# confBadgeV1.net
KiCad netlist of a schematic drawn in EAGLE
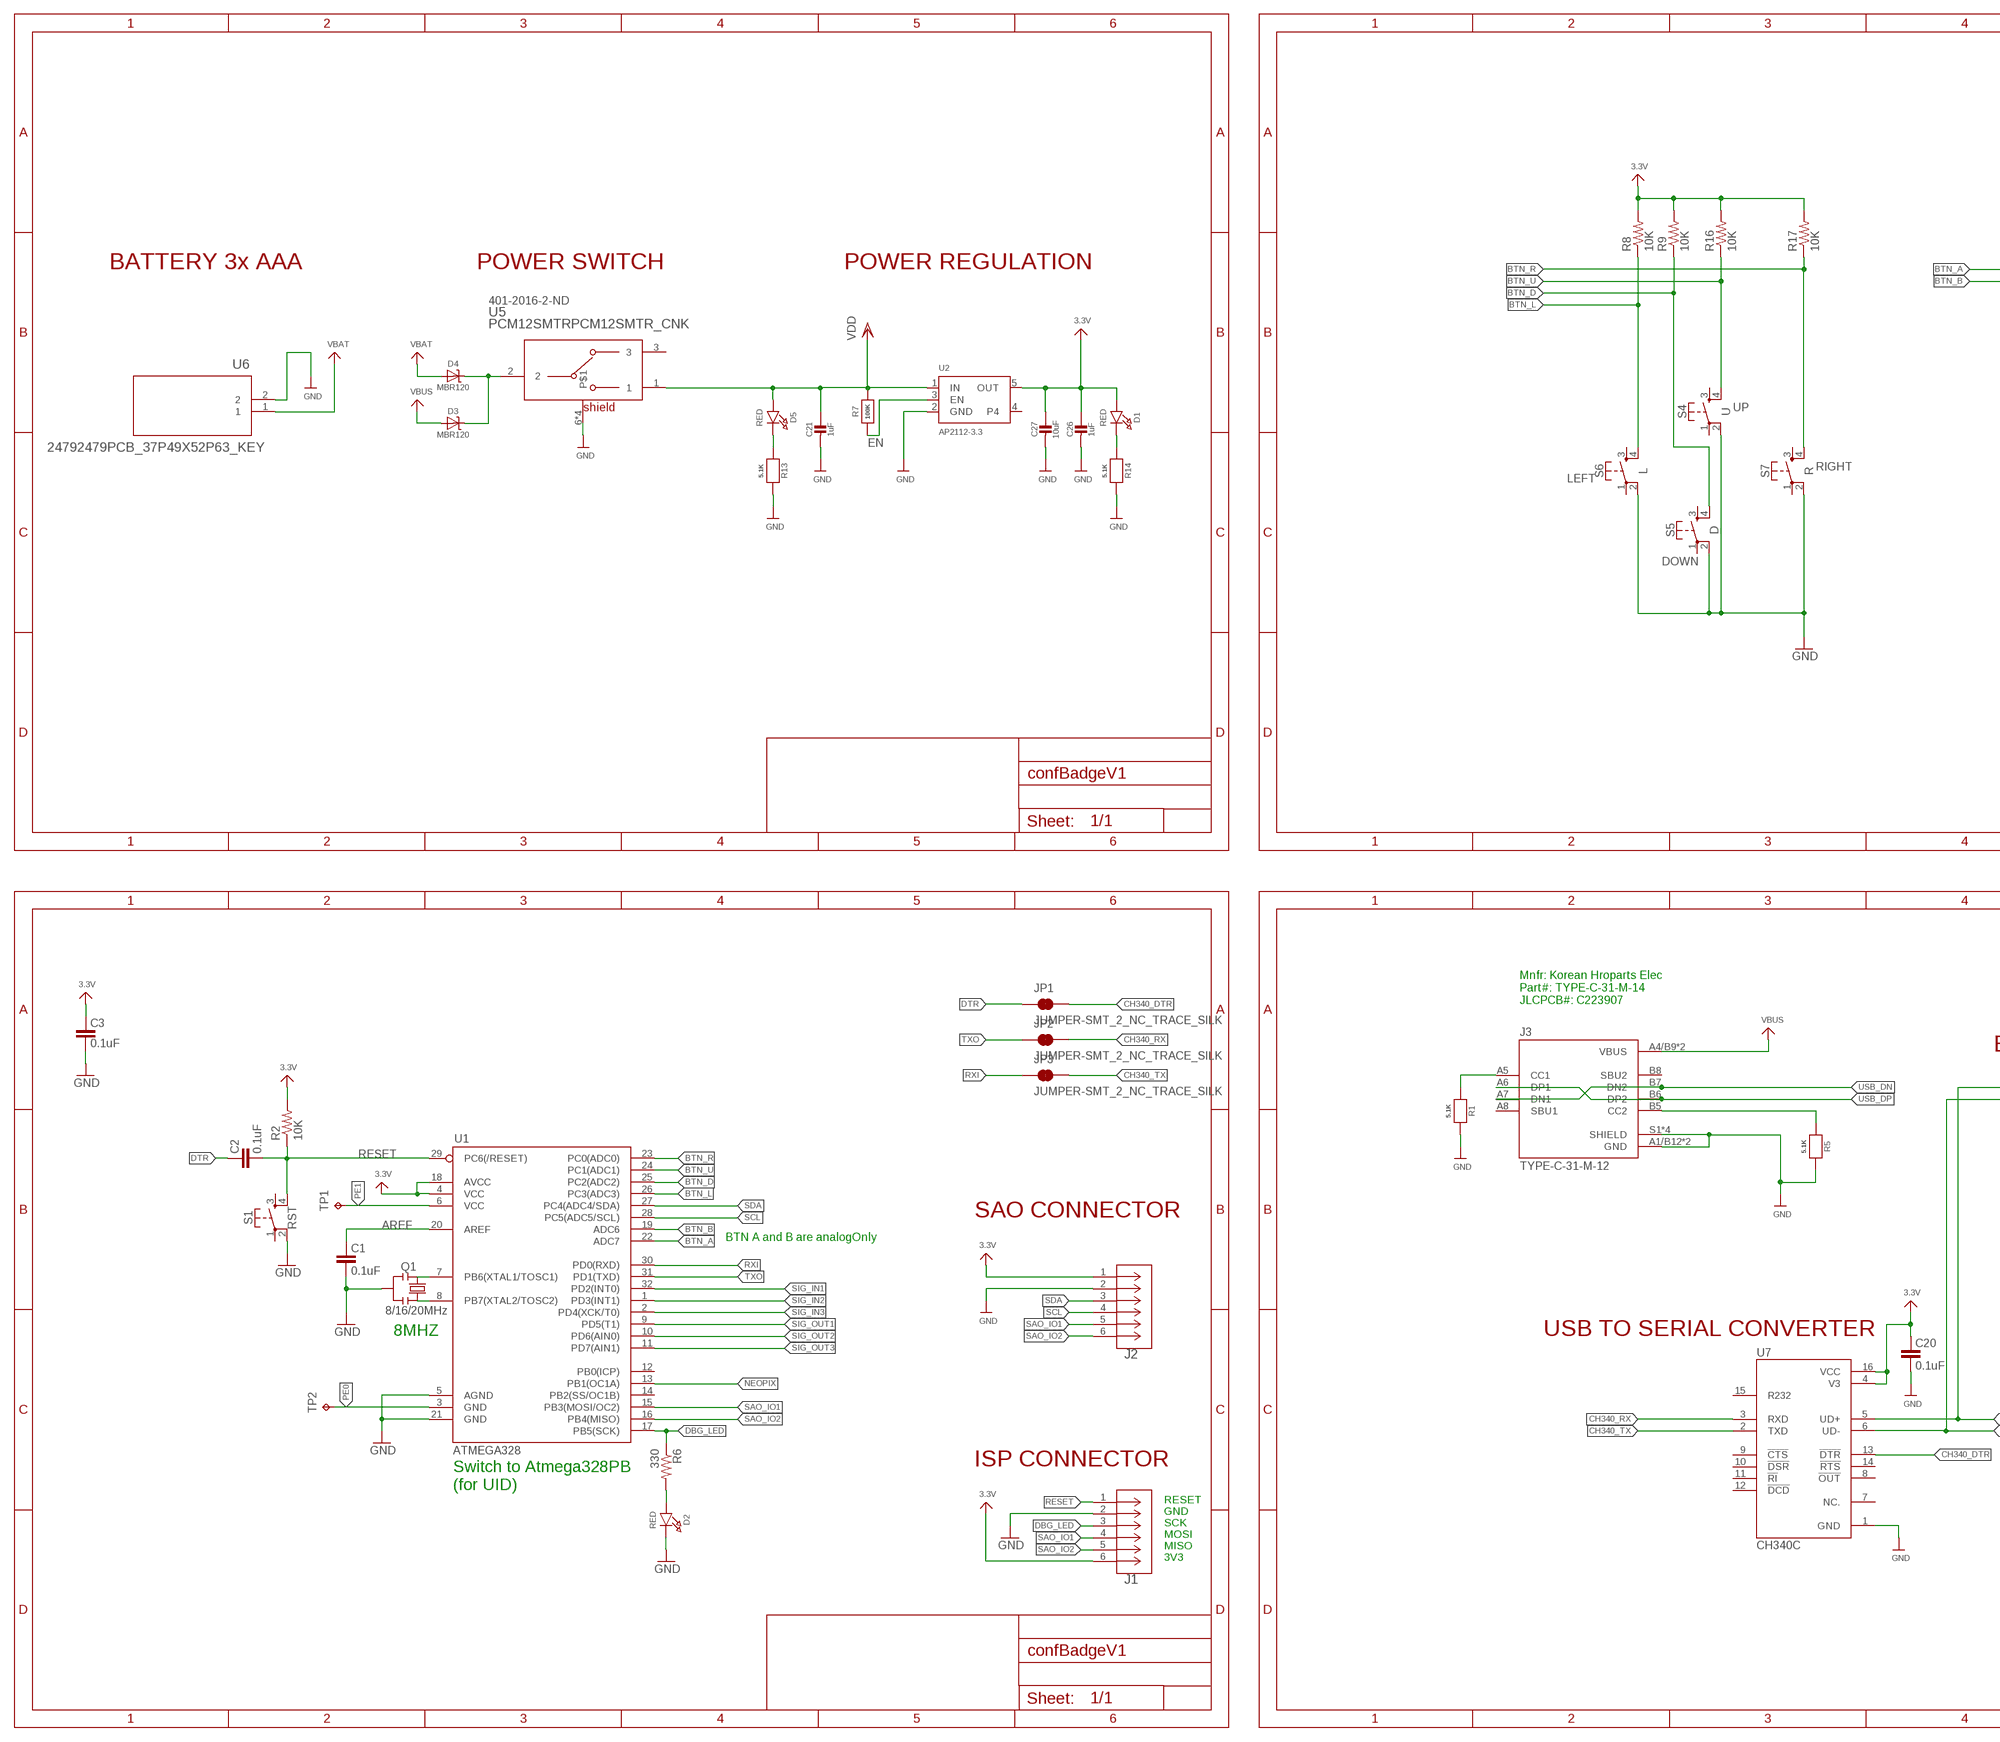
[diagram p0: schematic, sheet 1, part 1 of 2]
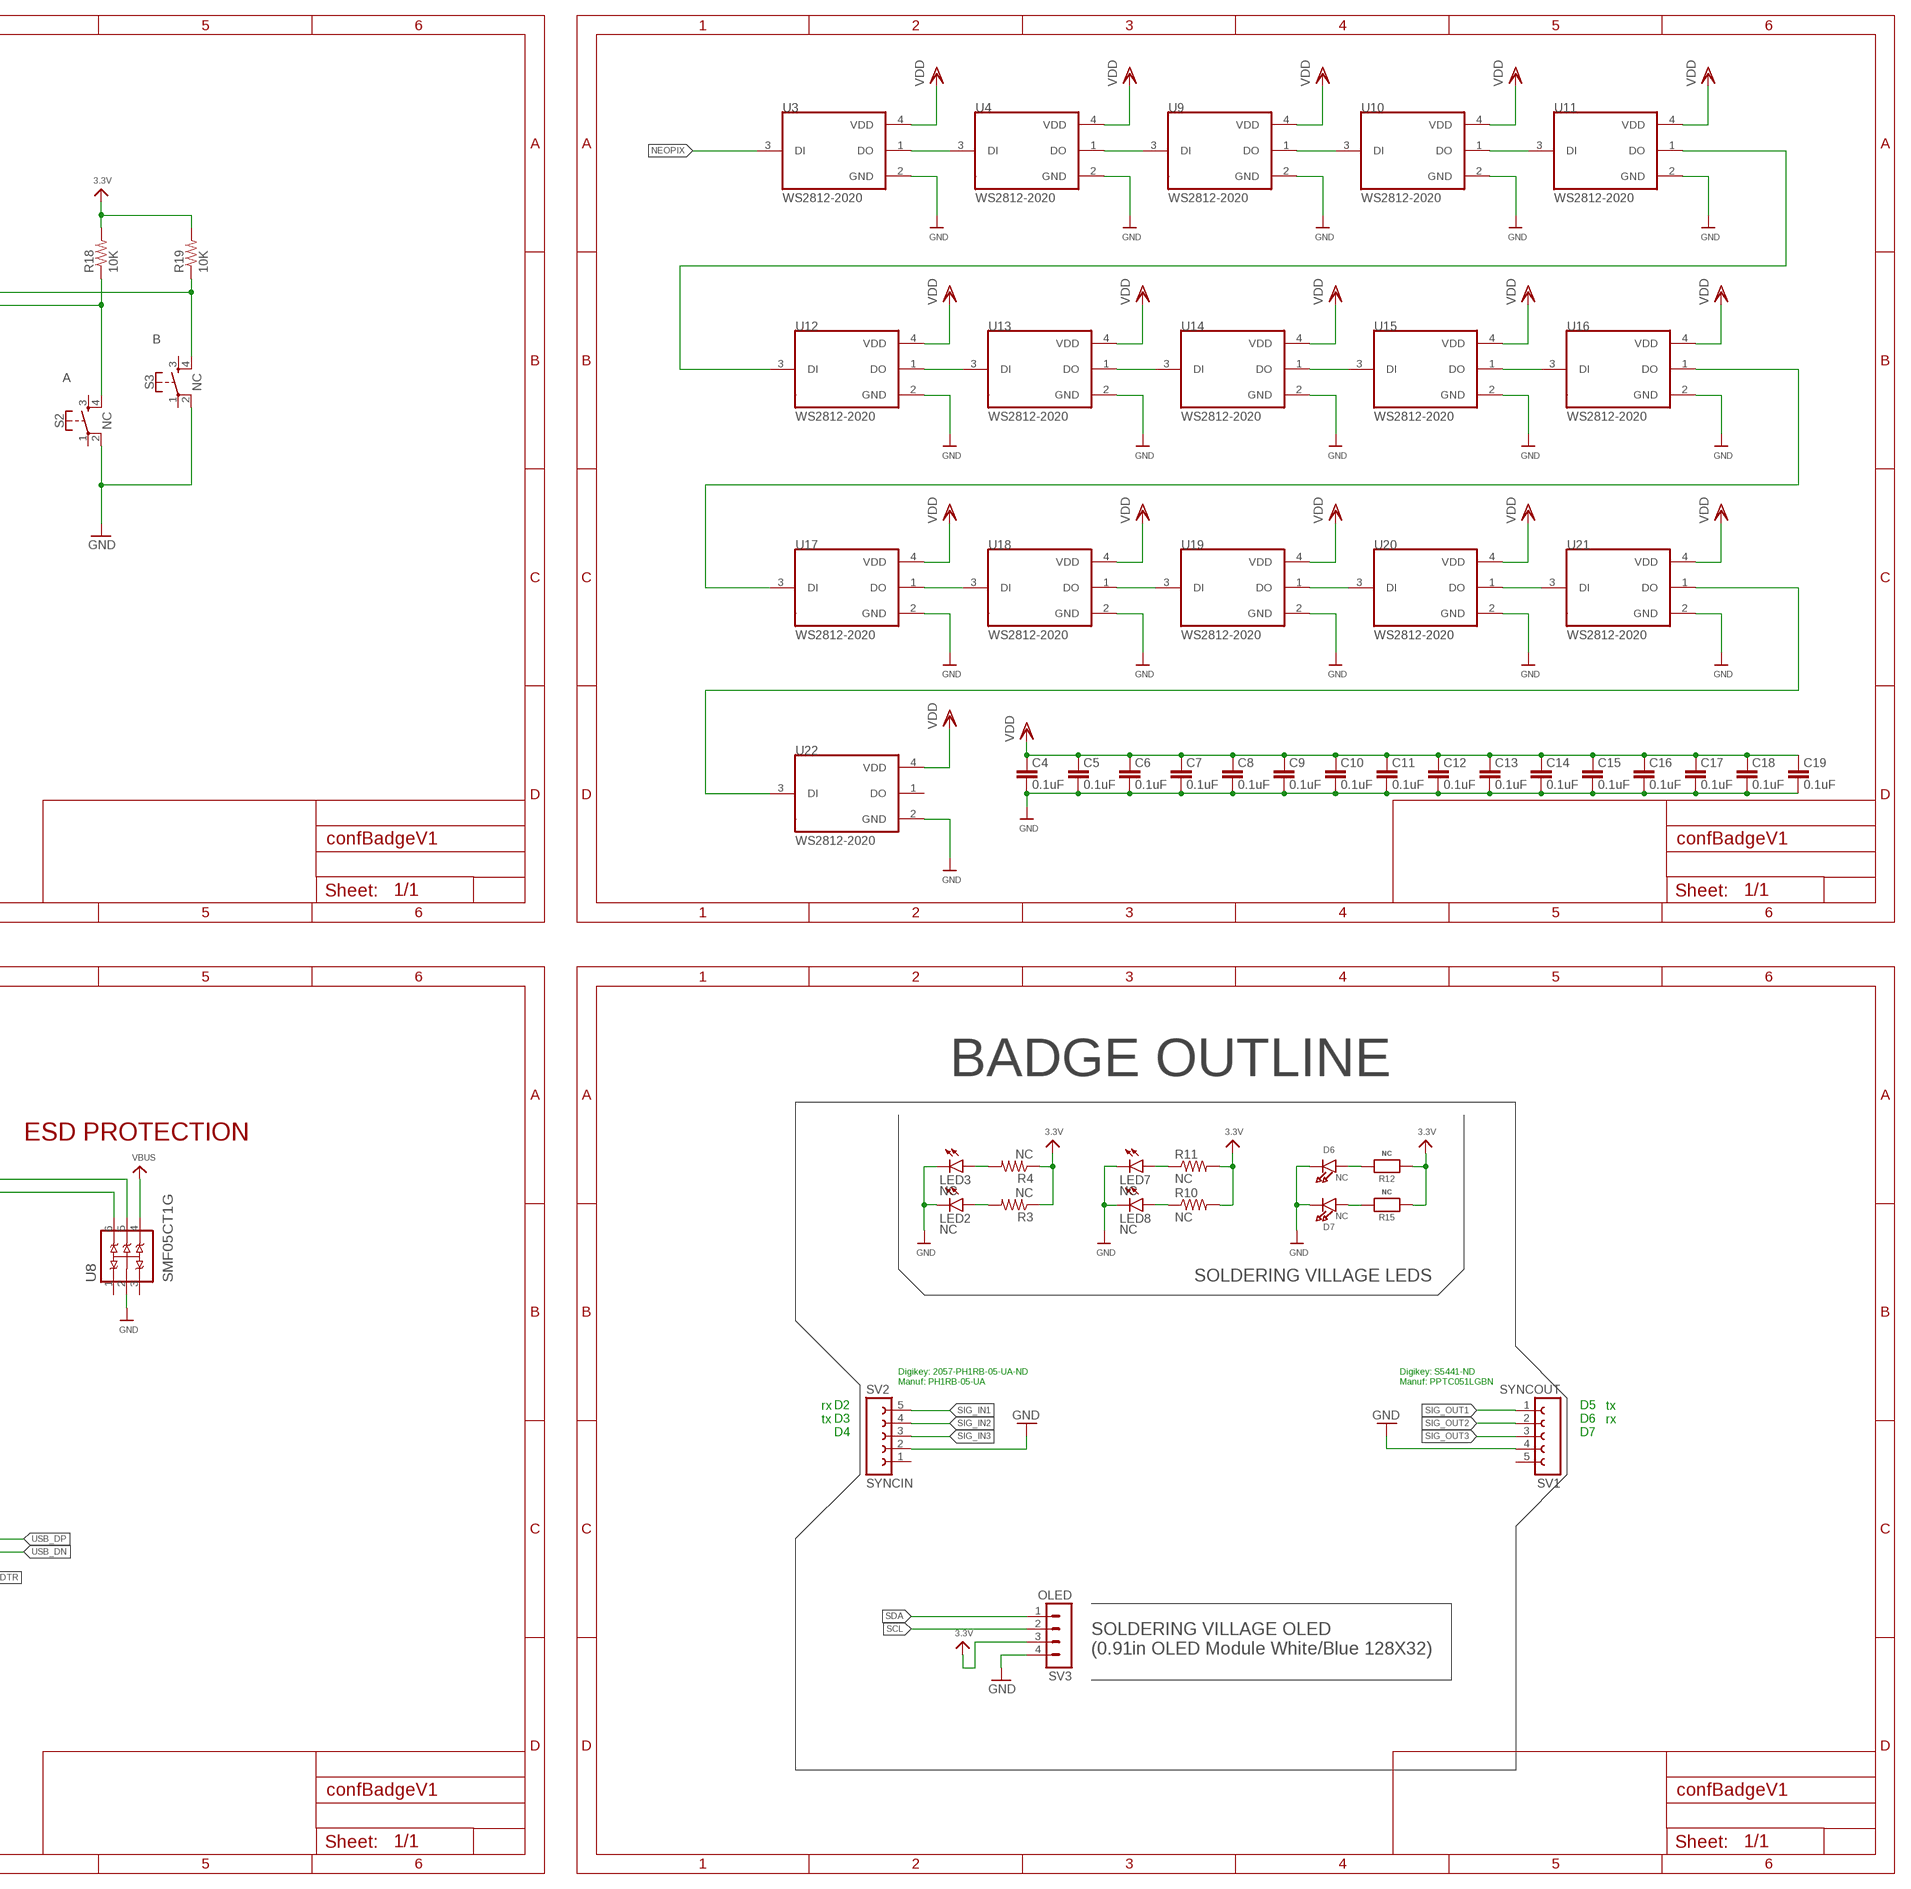
[diagram p1: schematic, sheet 1, part 2 of 2]

(export (version "E")
  (design (tool "Eeschema 10.0.6"))
  (components
    (comp (ref "C1")
      (value "0.1uF")
      (footprint "eagle-import:0603-CAP")
      (libsource (lib "eagle-import") (part "CAP0603-CAP"))
    )
    (comp (ref "C2")
      (value "0.1uF")
      (footprint "eagle-import:0603-CAP")
      (libsource (lib "eagle-import") (part "CAP0603-CAP"))
    )
    (comp (ref "C3")
      (value "0.1uF")
      (footprint "eagle-import:0603-CAP")
      (libsource (lib "eagle-import") (part "CAP0603-CAP"))
    )
    (comp (ref "C4")
      (value "0.1uF")
      (footprint "eagle-import:0603-CAP")
      (libsource (lib "eagle-import") (part "CAP0603-CAP"))
    )
    (comp (ref "C5")
      (value "0.1uF")
      (footprint "eagle-import:0603-CAP")
      (libsource (lib "eagle-import") (part "CAP0603-CAP"))
    )
    (comp (ref "C6")
      (value "0.1uF")
      (footprint "eagle-import:0603-CAP")
      (libsource (lib "eagle-import") (part "CAP0603-CAP"))
    )
    (comp (ref "C7")
      (value "0.1uF")
      (footprint "eagle-import:0603-CAP")
      (libsource (lib "eagle-import") (part "CAP0603-CAP"))
    )
    (comp (ref "C8")
      (value "0.1uF")
      (footprint "eagle-import:0603-CAP")
      (libsource (lib "eagle-import") (part "CAP0603-CAP"))
    )
    (comp (ref "C9")
      (value "0.1uF")
      (footprint "eagle-import:0603-CAP")
      (libsource (lib "eagle-import") (part "CAP0603-CAP"))
    )
    (comp (ref "C10")
      (value "0.1uF")
      (footprint "eagle-import:0603-CAP")
      (libsource (lib "eagle-import") (part "CAP0603-CAP"))
    )
    (comp (ref "C11")
      (value "0.1uF")
      (footprint "eagle-import:0603-CAP")
      (libsource (lib "eagle-import") (part "CAP0603-CAP"))
    )
    (comp (ref "C12")
      (value "0.1uF")
      (footprint "eagle-import:0603-CAP")
      (libsource (lib "eagle-import") (part "CAP0603-CAP"))
    )
    (comp (ref "C13")
      (value "0.1uF")
      (footprint "eagle-import:0603-CAP")
      (libsource (lib "eagle-import") (part "CAP0603-CAP"))
    )
    (comp (ref "C14")
      (value "0.1uF")
      (footprint "eagle-import:0603-CAP")
      (libsource (lib "eagle-import") (part "CAP0603-CAP"))
    )
    (comp (ref "C15")
      (value "0.1uF")
      (footprint "eagle-import:0603-CAP")
      (libsource (lib "eagle-import") (part "CAP0603-CAP"))
    )
    (comp (ref "C16")
      (value "0.1uF")
      (footprint "eagle-import:0603-CAP")
      (libsource (lib "eagle-import") (part "CAP0603-CAP"))
    )
    (comp (ref "C17")
      (value "0.1uF")
      (footprint "eagle-import:0603-CAP")
      (libsource (lib "eagle-import") (part "CAP0603-CAP"))
    )
    (comp (ref "C18")
      (value "0.1uF")
      (footprint "eagle-import:0603-CAP")
      (libsource (lib "eagle-import") (part "CAP0603-CAP"))
    )
    (comp (ref "C19")
      (value "0.1uF")
      (footprint "eagle-import:0603-CAP")
      (libsource (lib "eagle-import") (part "CAP0603-CAP"))
    )
    (comp (ref "C20")
      (value "0.1uF")
      (footprint "eagle-import:0603-CAP")
      (libsource (lib "eagle-import") (part "CAP0603-CAP"))
    )
    (comp (ref "C21")
      (value "1uF")
      (footprint "eagle-import:0603-NO")
      (libsource (lib "eagle-import") (part "CAP_CERAMIC0603_NO"))
    )
    (comp (ref "C26")
      (value "1uF")
      (footprint "eagle-import:0603-NO")
      (libsource (lib "eagle-import") (part "CAP_CERAMIC0603_NO"))
    )
    (comp (ref "C27")
      (value "10uF")
      (footprint "eagle-import:0805-NO")
      (libsource (lib "eagle-import") (part "CAP_CERAMIC0805-NOOUTLINE"))
    )
    (comp (ref "D1")
      (value "RED")
      (footprint "eagle-import:CHIPLED_0805_NOOUTLINE")
      (libsource (lib "eagle-import") (part "LED0805_NOOUTLINE"))
    )
    (comp (ref "D2")
      (value "RED")
      (footprint "eagle-import:CHIPLED_0805_NOOUTLINE")
      (libsource (lib "eagle-import") (part "LED0805_NOOUTLINE"))
    )
    (comp (ref "D3")
      (value "MBR120")
      (footprint "eagle-import:SOD-123")
      (libsource (lib "eagle-import") (part "DIODE-SCHOTTKYSOD-123"))
    )
    (comp (ref "D4")
      (value "MBR120")
      (footprint "eagle-import:SOD-123")
      (libsource (lib "eagle-import") (part "DIODE-SCHOTTKYSOD-123"))
    )
    (comp (ref "D5")
      (value "RED")
      (footprint "eagle-import:CHIPLED_0805_NOOUTLINE")
      (libsource (lib "eagle-import") (part "LED0805_NOOUTLINE"))
    )
    (comp (ref "D6")
      (value "NC")
      (footprint "eagle-import:CHIPLED_0805_NOOUTLINE")
      (libsource (lib "eagle-import") (part "LED0805_NOOUTLINE"))
    )
    (comp (ref "D7")
      (value "NC")
      (footprint "eagle-import:CHIPLED_0805_NOOUTLINE")
      (libsource (lib "eagle-import") (part "LED0805_NOOUTLINE"))
    )
    (comp (ref "J1")
      (value "SSW-103-22-F-D-VS-K-TRCON3_SSW-D-DUMZ_HDR_SAI")
      (footprint "eagle-import:CON3_SSW-D-DUMZ_HDR_SAI")
      (fields
        (field (name "MANUFACTURER_PART_NUMBER") "SSW-103-22-F-D-VS-K-TR")
        (field (name "COPYRIGHT") "Copyright (C) 2022 Ultra Librarian. All rights reserved.")
      )
      (libsource (lib "eagle-import") (part "SSW-103-22-F-D-VS-K-TRCON3_SSW-D-DUMZ_HDR_SAI"))
    )
    (comp (ref "J2")
      (value "SSW-103-22-F-D-VS-K-TRCON3_SSW-D-DUMZ_HDR_SAI")
      (footprint "eagle-import:CON3_SSW-D-DUMZ_HDR_SAI")
      (fields
        (field (name "MANUFACTURER_PART_NUMBER") "SSW-103-22-F-D-VS-K-TR")
        (field (name "COPYRIGHT") "Copyright (C) 2022 Ultra Librarian. All rights reserved.")
      )
      (libsource (lib "eagle-import") (part "SSW-103-22-F-D-VS-K-TRCON3_SSW-D-DUMZ_HDR_SAI"))
    )
    (comp (ref "J3")
      (value "TYPE-C-31-M-12")
      (footprint "eagle-import:HRO_TYPE-C-31-M-12")
      (fields (field (name "MANUFACTURER") "HRO Electronics Co., Ltd."))
      (libsource (lib "eagle-import") (part "TYPE-C-31-M-12"))
    )
    (comp (ref "JP1")
      (value "JUMPER-SMT_2_NC_TRACE_SILK")
      (footprint "eagle-import:SMT-JUMPER_2_NC_TRACE_SILK")
      (libsource (lib "eagle-import") (part "JUMPER-SMT_2_NC_TRACE_SILK"))
    )
    (comp (ref "JP2")
      (value "JUMPER-SMT_2_NC_TRACE_SILK")
      (footprint "eagle-import:SMT-JUMPER_2_NC_TRACE_SILK")
      (libsource (lib "eagle-import") (part "JUMPER-SMT_2_NC_TRACE_SILK"))
    )
    (comp (ref "JP3")
      (value "JUMPER-SMT_2_NC_TRACE_SILK")
      (footprint "eagle-import:SMT-JUMPER_2_NC_TRACE_SILK")
      (libsource (lib "eagle-import") (part "JUMPER-SMT_2_NC_TRACE_SILK"))
    )
    (comp (ref "LED2")
      (value "NC")
      (footprint "eagle-import:LED3MM")
      (libsource (lib "eagle-import") (part "LED3MM"))
    )
    (comp (ref "LED3")
      (value "NC")
      (footprint "eagle-import:LED3MM")
      (libsource (lib "eagle-import") (part "LED3MM"))
    )
    (comp (ref "LED7")
      (value "NC")
      (footprint "eagle-import:CHIPLED_1206")
      (libsource (lib "eagle-import") (part "LEDCHIPLED_1206"))
    )
    (comp (ref "LED8")
      (value "NC")
      (footprint "eagle-import:CHIPLED_1206")
      (libsource (lib "eagle-import") (part "LEDCHIPLED_1206"))
    )
    (comp (ref "Q1")
      (value "8/16/20MHz")
      (footprint "eagle-import:RESONATOR-SMD-1_1")
      (libsource (lib "eagle-import") (part "RESONATOR1{colon}1"))
    )
    (comp (ref "R1")
      (value "5.1K")
      (footprint "eagle-import:0603-NO")
      (libsource (lib "eagle-import") (part "RESISTOR_0603_NOOUT"))
    )
    (comp (ref "R2")
      (value "10K")
      (footprint "eagle-import:0603-RES")
      (libsource (lib "eagle-import") (part "RESISTOR0603-RES"))
    )
    (comp (ref "R3")
      (value "NC")
      (footprint "eagle-import:0207_10")
      (libsource (lib "eagle-import") (part "R-US_0207/10"))
    )
    (comp (ref "R4")
      (value "NC")
      (footprint "eagle-import:0207_10")
      (libsource (lib "eagle-import") (part "R-US_0207/10"))
    )
    (comp (ref "R5")
      (value "5.1K")
      (footprint "eagle-import:0603-NO")
      (libsource (lib "eagle-import") (part "RESISTOR_0603_NOOUT"))
    )
    (comp (ref "R6")
      (value "330")
      (footprint "eagle-import:0603-RES")
      (libsource (lib "eagle-import") (part "RESISTOR0603-RES"))
    )
    (comp (ref "R7")
      (value "100K")
      (footprint "eagle-import:0603-NO")
      (libsource (lib "eagle-import") (part "RESISTOR_0603_NOOUT"))
    )
    (comp (ref "R8")
      (value "10K")
      (footprint "eagle-import:0603-RES")
      (libsource (lib "eagle-import") (part "RESISTOR0603-RES"))
    )
    (comp (ref "R9")
      (value "10K")
      (footprint "eagle-import:0603-RES")
      (libsource (lib "eagle-import") (part "RESISTOR0603-RES"))
    )
    (comp (ref "R10")
      (value "NC")
      (footprint "eagle-import:R1206W")
      (libsource (lib "eagle-import") (part "R-US_R1206W"))
    )
    (comp (ref "R11")
      (value "NC")
      (footprint "eagle-import:R1206W")
      (libsource (lib "eagle-import") (part "R-US_R1206W"))
    )
    (comp (ref "R12")
      (value "NC")
      (footprint "eagle-import:0603-NO")
      (libsource (lib "eagle-import") (part "RESISTOR_0603_NOOUT"))
    )
    (comp (ref "R13")
      (value "5.1K")
      (footprint "eagle-import:0603-NO")
      (libsource (lib "eagle-import") (part "RESISTOR_0603_NOOUT"))
    )
    (comp (ref "R14")
      (value "5.1K")
      (footprint "eagle-import:0603-NO")
      (libsource (lib "eagle-import") (part "RESISTOR_0603_NOOUT"))
    )
    (comp (ref "R15")
      (value "NC")
      (footprint "eagle-import:0603-NO")
      (libsource (lib "eagle-import") (part "RESISTOR_0603_NOOUT"))
    )
    (comp (ref "R16")
      (value "10K")
      (footprint "eagle-import:0603-RES")
      (libsource (lib "eagle-import") (part "RESISTOR0603-RES"))
    )
    (comp (ref "R17")
      (value "10K")
      (footprint "eagle-import:0603-RES")
      (libsource (lib "eagle-import") (part "RESISTOR0603-RES"))
    )
    (comp (ref "R18")
      (value "10K")
      (footprint "eagle-import:0603-RES")
      (libsource (lib "eagle-import") (part "RESISTOR0603-RES"))
    )
    (comp (ref "R19")
      (value "10K")
      (footprint "eagle-import:0603-RES")
      (libsource (lib "eagle-import") (part "RESISTOR0603-RES"))
    )
    (comp (ref "S1")
      (value "RST")
      (footprint "eagle-import:TACTILE_SWITCH_SMD_5.2MM")
      (libsource (lib "eagle-import") (part "MOMENTARY-SWITCH-SPST-2-SMD-5.2MM"))
    )
    (comp (ref "S2")
      (value "NC")
      (footprint "eagle-import:TACTILE_SWITCH_SMD_5.2MM")
      (libsource (lib "eagle-import") (part "MOMENTARY-SWITCH-SPST-2-SMD-5.2MM"))
    )
    (comp (ref "S3")
      (value "NC")
      (footprint "eagle-import:TACTILE_SWITCH_SMD_5.2MM")
      (libsource (lib "eagle-import") (part "MOMENTARY-SWITCH-SPST-2-SMD-5.2MM"))
    )
    (comp (ref "S4")
      (value "U")
      (footprint "eagle-import:TACTILE_SWITCH_SMD_5.2MM")
      (libsource (lib "eagle-import") (part "MOMENTARY-SWITCH-SPST-2-SMD-5.2MM"))
    )
    (comp (ref "S5")
      (value "D")
      (footprint "eagle-import:TACTILE_SWITCH_SMD_5.2MM")
      (libsource (lib "eagle-import") (part "MOMENTARY-SWITCH-SPST-2-SMD-5.2MM"))
    )
    (comp (ref "S6")
      (value "L")
      (footprint "eagle-import:TACTILE_SWITCH_SMD_5.2MM")
      (libsource (lib "eagle-import") (part "MOMENTARY-SWITCH-SPST-2-SMD-5.2MM"))
    )
    (comp (ref "S7")
      (value "R")
      (footprint "eagle-import:TACTILE_SWITCH_SMD_5.2MM")
      (libsource (lib "eagle-import") (part "MOMENTARY-SWITCH-SPST-2-SMD-5.2MM"))
    )
    (comp (ref "SV1")
      (value "SYNCOUT")
      (footprint "eagle-import:FE05W")
      (libsource (lib "eagle-import") (part "FE05W"))
    )
    (comp (ref "SV2")
      (value "SYNCIN")
      (footprint "eagle-import:FE05W")
      (libsource (lib "eagle-import") (part "FE05W"))
    )
    (comp (ref "SV3")
      (value "OLED")
      (footprint "eagle-import:MA04-1")
      (libsource (lib "eagle-import") (part "MA04-1"))
    )
    (comp (ref "TP1")
      (value "TPB1,27")
      (footprint "eagle-import:B1,27")
      (libsource (lib "eagle-import") (part "TPB1,27"))
    )
    (comp (ref "TP2")
      (value "TPB1,27")
      (footprint "eagle-import:B1,27")
      (libsource (lib "eagle-import") (part "TPB1,27"))
    )
    (comp (ref "U1")
      (value "ATMEGA328")
      (footprint "eagle-import:TQFP32-08")
      (libsource (lib "eagle-import") (part "ATMEGA168"))
    )
    (comp (ref "U2")
      (value "AP2112-3.3")
      (footprint "eagle-import:SOT23-5")
      (libsource (lib "eagle-import") (part "VREG_SOT23-5"))
    )
    (comp (ref "U3")
      (value "WS2812-2020")
      (footprint "eagle-import:LED_WS2812-2020")
      (fields (field (name "MF") "Worldsemi"))
      (libsource (lib "eagle-import") (part "WS2812-2020"))
    )
    (comp (ref "U4")
      (value "WS2812-2020")
      (footprint "eagle-import:LED_WS2812-2020")
      (fields (field (name "MF") "Worldsemi"))
      (libsource (lib "eagle-import") (part "WS2812-2020"))
    )
    (comp (ref "U5")
      (value "PCM12SMTRPCM12SMTR_CNK")
      (footprint "eagle-import:PCM12SMTR_CNK")
      (fields
        (field (name "MANUFACTURER_PART_NUMBER") "PCM12SMTR")
        (field (name "COPYRIGHT") "Copyright (C) 2022 Ultra Librarian. All rights reserved.")
      )
      (libsource (lib "eagle-import") (part "PCM12SMTRPCM12SMTR_CNK"))
    )
    (comp (ref "U6")
      (value "24792479PCB_37P49X52P63_KEY")
      (footprint "eagle-import:2479PCB_37P49X52P63_KEY")
      (fields
        (field (name "MANUFACTURER_PART_NUMBER") "2479")
        (field (name "COPYRIGHT") "Copyright (C) 2022 Ultra Librarian. All rights reserved.")
      )
      (libsource (lib "eagle-import") (part "24792479PCB_37P49X52P63_KEY"))
    )
    (comp (ref "U7")
      (value "CH340C")
      (footprint "eagle-import:SOIC127P600X180-16N")
      (fields (field (name "MF") "WCH"))
      (libsource (lib "eagle-import") (part "CH340C"))
    )
    (comp (ref "U8")
      (value "SMF05CT1G")
      (footprint "eagle-import:SOT65P210X110-6N")
      (fields (field (name "MF") "ON Semiconductor"))
      (libsource (lib "eagle-import") (part "SMF05CT1G"))
    )
    (comp (ref "U9")
      (value "WS2812-2020")
      (footprint "eagle-import:LED_WS2812-2020")
      (fields (field (name "MF") "Worldsemi"))
      (libsource (lib "eagle-import") (part "WS2812-2020"))
    )
    (comp (ref "U10")
      (value "WS2812-2020")
      (footprint "eagle-import:LED_WS2812-2020")
      (fields (field (name "MF") "Worldsemi"))
      (libsource (lib "eagle-import") (part "WS2812-2020"))
    )
    (comp (ref "U11")
      (value "WS2812-2020")
      (footprint "eagle-import:LED_WS2812-2020")
      (fields (field (name "MF") "Worldsemi"))
      (libsource (lib "eagle-import") (part "WS2812-2020"))
    )
    (comp (ref "U12")
      (value "WS2812-2020")
      (footprint "eagle-import:LED_WS2812-2020")
      (fields (field (name "MF") "Worldsemi"))
      (libsource (lib "eagle-import") (part "WS2812-2020"))
    )
    (comp (ref "U13")
      (value "WS2812-2020")
      (footprint "eagle-import:LED_WS2812-2020")
      (fields (field (name "MF") "Worldsemi"))
      (libsource (lib "eagle-import") (part "WS2812-2020"))
    )
    (comp (ref "U14")
      (value "WS2812-2020")
      (footprint "eagle-import:LED_WS2812-2020")
      (fields (field (name "MF") "Worldsemi"))
      (libsource (lib "eagle-import") (part "WS2812-2020"))
    )
    (comp (ref "U15")
      (value "WS2812-2020")
      (footprint "eagle-import:LED_WS2812-2020")
      (fields (field (name "MF") "Worldsemi"))
      (libsource (lib "eagle-import") (part "WS2812-2020"))
    )
    (comp (ref "U16")
      (value "WS2812-2020")
      (footprint "eagle-import:LED_WS2812-2020")
      (fields (field (name "MF") "Worldsemi"))
      (libsource (lib "eagle-import") (part "WS2812-2020"))
    )
    (comp (ref "U17")
      (value "WS2812-2020")
      (footprint "eagle-import:LED_WS2812-2020")
      (fields (field (name "MF") "Worldsemi"))
      (libsource (lib "eagle-import") (part "WS2812-2020"))
    )
    (comp (ref "U18")
      (value "WS2812-2020")
      (footprint "eagle-import:LED_WS2812-2020")
      (fields (field (name "MF") "Worldsemi"))
      (libsource (lib "eagle-import") (part "WS2812-2020"))
    )
    (comp (ref "U19")
      (value "WS2812-2020")
      (footprint "eagle-import:LED_WS2812-2020")
      (fields (field (name "MF") "Worldsemi"))
      (libsource (lib "eagle-import") (part "WS2812-2020"))
    )
    (comp (ref "U20")
      (value "WS2812-2020")
      (footprint "eagle-import:LED_WS2812-2020")
      (fields (field (name "MF") "Worldsemi"))
      (libsource (lib "eagle-import") (part "WS2812-2020"))
    )
    (comp (ref "U21")
      (value "WS2812-2020")
      (footprint "eagle-import:LED_WS2812-2020")
      (fields (field (name "MF") "Worldsemi"))
      (libsource (lib "eagle-import") (part "WS2812-2020"))
    )
    (comp (ref "U22")
      (value "WS2812-2020")
      (footprint "eagle-import:LED_WS2812-2020")
      (fields (field (name "MF") "Worldsemi"))
      (libsource (lib "eagle-import") (part "WS2812-2020"))
    )
  )
  (nets
    (net (code "1") (name "/AREF") (class "Default")
      (node (ref "C1") (pin "2") (pinfunction "2_2") (pintype "passive"))
      (node (ref "U1") (pin "20") (pinfunction "AREF_20") (pintype "bidirectional"))
    )
    (net (code "2") (name "/EN") (class "Default")
      (node (ref "R7") (pin "1") (pinfunction "1_1") (pintype "passive"))
      (node (ref "U2") (pin "3") (pinfunction "EN_3") (pintype "input"))
    )
    (net (code "3") (name "3.3V") (class "Default")
      (node (ref "C20") (pin "2") (pinfunction "2_2") (pintype "passive"))
      (node (ref "C26") (pin "1") (pinfunction "1_1") (pintype "passive"))
      (node (ref "C27") (pin "1") (pinfunction "1_1") (pintype "passive"))
      (node (ref "C3") (pin "2") (pinfunction "2_2") (pintype "passive"))
      (node (ref "D1") (pin "A") (pinfunction "A_A") (pintype "passive"))
      (node (ref "J1") (pin "6") (pinfunction "6_6") (pintype "passive"))
      (node (ref "J2") (pin "1") (pinfunction "1_1") (pintype "passive"))
      (node (ref "R10") (pin "2") (pinfunction "2_2") (pintype "passive"))
      (node (ref "R11") (pin "2") (pinfunction "2_2") (pintype "passive"))
      (node (ref "R12") (pin "1") (pinfunction "1_1") (pintype "passive"))
      (node (ref "R15") (pin "1") (pinfunction "1_1") (pintype "passive"))
      (node (ref "R16") (pin "2") (pinfunction "2_2") (pintype "passive"))
      (node (ref "R17") (pin "2") (pinfunction "2_2") (pintype "passive"))
      (node (ref "R18") (pin "2") (pinfunction "2_2") (pintype "passive"))
      (node (ref "R19") (pin "2") (pinfunction "2_2") (pintype "passive"))
      (node (ref "R2") (pin "2") (pinfunction "2_2") (pintype "passive"))
      (node (ref "R3") (pin "1") (pinfunction "1_1") (pintype "passive"))
      (node (ref "R4") (pin "1") (pinfunction "1_1") (pintype "passive"))
      (node (ref "R8") (pin "2") (pinfunction "2_2") (pintype "passive"))
      (node (ref "R9") (pin "2") (pinfunction "2_2") (pintype "passive"))
      (node (ref "SV3") (pin "3") (pinfunction "3_3") (pintype "passive"))
      (node (ref "U1") (pin "18") (pinfunction "AVCC_18") (pintype "bidirectional"))
      (node (ref "U1") (pin "4") (pinfunction "VCC_4") (pintype "bidirectional"))
      (node (ref "U2") (pin "5") (pinfunction "OUT_5") (pintype "power_in"))
      (node (ref "U7") (pin "16") (pinfunction "VCC_16") (pintype "power_in"))
      (node (ref "U7") (pin "4") (pinfunction "V3_4") (pintype "power_in"))
    )
    (net (code "4") (name "BTN_A") (class "Default")
      (node (ref "R19") (pin "1") (pinfunction "1_1") (pintype "passive"))
      (node (ref "S3") (pin "4") (pinfunction "4_4") (pintype "passive"))
      (node (ref "U1") (pin "22") (pinfunction "ADC7_22") (pintype "bidirectional"))
    )
    (net (code "5") (name "BTN_B") (class "Default")
      (node (ref "R18") (pin "1") (pinfunction "1_1") (pintype "passive"))
      (node (ref "S2") (pin "4") (pinfunction "4_4") (pintype "passive"))
      (node (ref "U1") (pin "19") (pinfunction "ADC6_19") (pintype "bidirectional"))
    )
    (net (code "6") (name "BTN_D") (class "Default")
      (node (ref "R9") (pin "1") (pinfunction "1_1") (pintype "passive"))
      (node (ref "S5") (pin "4") (pinfunction "4_4") (pintype "passive"))
      (node (ref "U1") (pin "25") (pinfunction "PC2(ADC2)_25") (pintype "bidirectional"))
    )
    (net (code "7") (name "BTN_L") (class "Default")
      (node (ref "R8") (pin "1") (pinfunction "1_1") (pintype "passive"))
      (node (ref "S6") (pin "4") (pinfunction "4_4") (pintype "passive"))
      (node (ref "U1") (pin "26") (pinfunction "PC3(ADC3)_26") (pintype "bidirectional"))
    )
    (net (code "8") (name "BTN_R") (class "Default")
      (node (ref "R17") (pin "1") (pinfunction "1_1") (pintype "passive"))
      (node (ref "S7") (pin "4") (pinfunction "4_4") (pintype "passive"))
      (node (ref "U1") (pin "23") (pinfunction "PC0(ADC0)_23") (pintype "bidirectional"))
    )
    (net (code "9") (name "BTN_U") (class "Default")
      (node (ref "R16") (pin "1") (pinfunction "1_1") (pintype "passive"))
      (node (ref "S4") (pin "4") (pinfunction "4_4") (pintype "passive"))
      (node (ref "U1") (pin "24") (pinfunction "PC1(ADC1)_24") (pintype "bidirectional"))
    )
    (net (code "10") (name "CH340_DTR") (class "Default")
      (node (ref "JP1") (pin "2") (pinfunction "2_2") (pintype "passive"))
      (node (ref "U7") (pin "13") (pinfunction "~{DTR}_13") (pintype "output"))
    )
    (net (code "11") (name "CH340_RX") (class "Default")
      (node (ref "JP2") (pin "2") (pinfunction "2_2") (pintype "passive"))
      (node (ref "U7") (pin "3") (pinfunction "RXD_3") (pintype "input"))
    )
    (net (code "12") (name "CH340_TX") (class "Default")
      (node (ref "JP3") (pin "2") (pinfunction "2_2") (pintype "passive"))
      (node (ref "U7") (pin "2") (pinfunction "TXD_2") (pintype "output"))
    )
    (net (code "13") (name "DBG_LED") (class "Default")
      (node (ref "J1") (pin "3") (pinfunction "3_3") (pintype "passive"))
      (node (ref "R6") (pin "1") (pinfunction "1_1") (pintype "passive"))
      (node (ref "U1") (pin "17") (pinfunction "PB5(SCK)_17") (pintype "bidirectional"))
    )
    (net (code "14") (name "DTR") (class "Default")
      (node (ref "C2") (pin "2") (pinfunction "2_2") (pintype "passive"))
      (node (ref "JP1") (pin "1") (pinfunction "1_1") (pintype "passive"))
    )
    (net (code "15") (name "GND") (class "Default")
      (node (ref "C1") (pin "1") (pinfunction "1_1") (pintype "passive"))
      (node (ref "C10") (pin "1") (pinfunction "1_1") (pintype "passive"))
      (node (ref "C11") (pin "1") (pinfunction "1_1") (pintype "passive"))
      (node (ref "C12") (pin "1") (pinfunction "1_1") (pintype "passive"))
      (node (ref "C13") (pin "1") (pinfunction "1_1") (pintype "passive"))
      (node (ref "C14") (pin "1") (pinfunction "1_1") (pintype "passive"))
      (node (ref "C15") (pin "1") (pinfunction "1_1") (pintype "passive"))
      (node (ref "C16") (pin "1") (pinfunction "1_1") (pintype "passive"))
      (node (ref "C17") (pin "1") (pinfunction "1_1") (pintype "passive"))
      (node (ref "C18") (pin "1") (pinfunction "1_1") (pintype "passive"))
      (node (ref "C19") (pin "1") (pinfunction "1_1") (pintype "passive"))
      (node (ref "C20") (pin "1") (pinfunction "1_1") (pintype "passive"))
      (node (ref "C21") (pin "2") (pinfunction "2_2") (pintype "passive"))
      (node (ref "C26") (pin "2") (pinfunction "2_2") (pintype "passive"))
      (node (ref "C27") (pin "2") (pinfunction "2_2") (pintype "passive"))
      (node (ref "C3") (pin "1") (pinfunction "1_1") (pintype "passive"))
      (node (ref "C4") (pin "1") (pinfunction "1_1") (pintype "passive"))
      (node (ref "C5") (pin "1") (pinfunction "1_1") (pintype "passive"))
      (node (ref "C6") (pin "1") (pinfunction "1_1") (pintype "passive"))
      (node (ref "C7") (pin "1") (pinfunction "1_1") (pintype "passive"))
      (node (ref "C8") (pin "1") (pinfunction "1_1") (pintype "passive"))
      (node (ref "C9") (pin "1") (pinfunction "1_1") (pintype "passive"))
      (node (ref "D2") (pin "C") (pinfunction "C_C") (pintype "passive"))
      (node (ref "D6") (pin "C") (pinfunction "C_C") (pintype "passive"))
      (node (ref "D7") (pin "C") (pinfunction "C_C") (pintype "passive"))
      (node (ref "J1") (pin "2") (pinfunction "2_2") (pintype "passive"))
      (node (ref "J2") (pin "2") (pinfunction "2_2") (pintype "passive"))
      (node (ref "J3") (pin "A1/B12") (pinfunction "GND_A1/B12") (pintype "power_in"))
      (node (ref "J3") (pin "B1/A12") (pinfunction "GND_B1/A12") (pintype "power_in"))
      (node (ref "J3") (pin "S1") (pinfunction "SHIELD_S1") (pintype "passive"))
      (node (ref "J3") (pin "S2") (pinfunction "SHIELD_S2") (pintype "passive"))
      (node (ref "J3") (pin "S3") (pinfunction "SHIELD_S3") (pintype "passive"))
      (node (ref "J3") (pin "S4") (pinfunction "SHIELD_S4") (pintype "passive"))
      (node (ref "LED2") (pin "K") (pinfunction "C_K") (pintype "passive"))
      (node (ref "LED3") (pin "K") (pinfunction "C_K") (pintype "passive"))
      (node (ref "LED7") (pin "C") (pinfunction "C_C") (pintype "passive"))
      (node (ref "LED8") (pin "C") (pinfunction "C_C") (pintype "passive"))
      (node (ref "Q1") (pin "2") (pinfunction "2_2") (pintype "passive"))
      (node (ref "R1") (pin "2") (pinfunction "2_2") (pintype "passive"))
      (node (ref "R13") (pin "2") (pinfunction "2_2") (pintype "passive"))
      (node (ref "R14") (pin "2") (pinfunction "2_2") (pintype "passive"))
      (node (ref "R5") (pin "2") (pinfunction "2_2") (pintype "passive"))
      (node (ref "S1") (pin "2") (pinfunction "2_2") (pintype "passive"))
      (node (ref "S2") (pin "2") (pinfunction "2_2") (pintype "passive"))
      (node (ref "S3") (pin "2") (pinfunction "2_2") (pintype "passive"))
      (node (ref "S4") (pin "2") (pinfunction "2_2") (pintype "passive"))
      (node (ref "S5") (pin "2") (pinfunction "2_2") (pintype "passive"))
      (node (ref "S6") (pin "2") (pinfunction "2_2") (pintype "passive"))
      (node (ref "S7") (pin "2") (pinfunction "2_2") (pintype "passive"))
      (node (ref "SV1") (pin "4") (pinfunction "4_4") (pintype "passive"))
      (node (ref "SV2") (pin "2") (pinfunction "2_2") (pintype "passive"))
      (node (ref "SV3") (pin "4") (pinfunction "4_4") (pintype "passive"))
      (node (ref "U1") (pin "21") (pinfunction "GND_21") (pintype "bidirectional"))
      (node (ref "U1") (pin "5") (pinfunction "AGND_5") (pintype "bidirectional"))
      (node (ref "U10") (pin "2") (pinfunction "GND_2") (pintype "power_in"))
      (node (ref "U11") (pin "2") (pinfunction "GND_2") (pintype "power_in"))
      (node (ref "U12") (pin "2") (pinfunction "GND_2") (pintype "power_in"))
      (node (ref "U13") (pin "2") (pinfunction "GND_2") (pintype "power_in"))
      (node (ref "U14") (pin "2") (pinfunction "GND_2") (pintype "power_in"))
      (node (ref "U15") (pin "2") (pinfunction "GND_2") (pintype "power_in"))
      (node (ref "U16") (pin "2") (pinfunction "GND_2") (pintype "power_in"))
      (node (ref "U17") (pin "2") (pinfunction "GND_2") (pintype "power_in"))
      (node (ref "U18") (pin "2") (pinfunction "GND_2") (pintype "power_in"))
      (node (ref "U19") (pin "2") (pinfunction "GND_2") (pintype "power_in"))
      (node (ref "U2") (pin "2") (pinfunction "GND_2") (pintype "power_in"))
      (node (ref "U20") (pin "2") (pinfunction "GND_2") (pintype "power_in"))
      (node (ref "U21") (pin "2") (pinfunction "GND_2") (pintype "power_in"))
      (node (ref "U22") (pin "2") (pinfunction "GND_2") (pintype "power_in"))
      (node (ref "U3") (pin "2") (pinfunction "GND_2") (pintype "power_in"))
      (node (ref "U4") (pin "2") (pinfunction "GND_2") (pintype "power_in"))
      (node (ref "U5") (pin "6") (pinfunction "P$1_6") (pintype "bidirectional"))
      (node (ref "U5") (pin "7") (pinfunction "P$1_7") (pintype "bidirectional"))
      (node (ref "U5") (pin "8") (pinfunction "P$1_8") (pintype "bidirectional"))
      (node (ref "U5") (pin "9") (pinfunction "P$1_9") (pintype "bidirectional"))
      (node (ref "U6") (pin "2") (pinfunction "2_2") (pintype "passive"))
      (node (ref "U7") (pin "1") (pinfunction "GND_1") (pintype "power_in"))
      (node (ref "U8") (pin "2") (pinfunction "A_2") (pintype "passive"))
      (node (ref "U9") (pin "2") (pinfunction "GND_2") (pintype "power_in"))
    )
    (net (code "16") (name "NEOPIX") (class "Default")
      (node (ref "U1") (pin "13") (pinfunction "PB1(OC1A)_13") (pintype "bidirectional"))
      (node (ref "U3") (pin "3") (pinfunction "DI_3") (pintype "input"))
    )
    (net (code "17") (name "Net-(D1-PadC)") (class "Default")
      (node (ref "D1") (pin "C") (pinfunction "C_C") (pintype "passive"))
      (node (ref "R14") (pin "1") (pinfunction "1_1") (pintype "passive"))
    )
    (net (code "18") (name "Net-(D2-PadA)") (class "Default")
      (node (ref "D2") (pin "A") (pinfunction "A_A") (pintype "passive"))
      (node (ref "R6") (pin "2") (pinfunction "2_2") (pintype "passive"))
    )
    (net (code "19") (name "Net-(D3-PadC)") (class "Default")
      (node (ref "D3") (pin "C") (pinfunction "C_C") (pintype "passive"))
      (node (ref "D4") (pin "C") (pinfunction "C_C") (pintype "passive"))
      (node (ref "U5") (pin "2") (pinfunction "2_2") (pintype "passive"))
    )
    (net (code "20") (name "Net-(D5-PadC)") (class "Default")
      (node (ref "D5") (pin "C") (pinfunction "C_C") (pintype "passive"))
      (node (ref "R13") (pin "1") (pinfunction "1_1") (pintype "passive"))
    )
    (net (code "21") (name "Net-(D6-PadA)") (class "Default")
      (node (ref "D6") (pin "A") (pinfunction "A_A") (pintype "passive"))
      (node (ref "R12") (pin "2") (pinfunction "2_2") (pintype "passive"))
    )
    (net (code "22") (name "Net-(D7-PadA)") (class "Default")
      (node (ref "D7") (pin "A") (pinfunction "A_A") (pintype "passive"))
      (node (ref "R15") (pin "2") (pinfunction "2_2") (pintype "passive"))
    )
    (net (code "23") (name "Net-(J3-CC1)") (class "Default")
      (node (ref "J3") (pin "A5") (pinfunction "CC1_A5") (pintype "bidirectional"))
      (node (ref "R1") (pin "1") (pinfunction "1_1") (pintype "passive"))
    )
    (net (code "24") (name "Net-(J3-CC2)") (class "Default")
      (node (ref "J3") (pin "B5") (pinfunction "CC2_B5") (pintype "bidirectional"))
      (node (ref "R5") (pin "1") (pinfunction "1_1") (pintype "passive"))
    )
    (net (code "25") (name "Net-(LED2-PadA)") (class "Default")
      (node (ref "LED2") (pin "A") (pinfunction "A_A") (pintype "passive"))
      (node (ref "R3") (pin "2") (pinfunction "2_2") (pintype "passive"))
    )
    (net (code "26") (name "Net-(LED3-PadA)") (class "Default")
      (node (ref "LED3") (pin "A") (pinfunction "A_A") (pintype "passive"))
      (node (ref "R4") (pin "2") (pinfunction "2_2") (pintype "passive"))
    )
    (net (code "27") (name "Net-(LED7-PadA)") (class "Default")
      (node (ref "LED7") (pin "A") (pinfunction "A_A") (pintype "passive"))
      (node (ref "R11") (pin "1") (pinfunction "1_1") (pintype "passive"))
    )
    (net (code "28") (name "Net-(LED8-PadA)") (class "Default")
      (node (ref "LED8") (pin "A") (pinfunction "A_A") (pintype "passive"))
      (node (ref "R10") (pin "1") (pinfunction "1_1") (pintype "passive"))
    )
    (net (code "29") (name "Net-(U1-PB6(XTAL1{slash}TOSC1))") (class "Default")
      (node (ref "Q1") (pin "1") (pinfunction "1_1") (pintype "passive"))
      (node (ref "U1") (pin "7") (pinfunction "PB6(XTAL1/TOSC1)_7") (pintype "bidirectional"))
    )
    (net (code "30") (name "Net-(U1-PB7(XTAL2{slash}TOSC2))") (class "Default")
      (node (ref "Q1") (pin "3") (pinfunction "3_3") (pintype "passive"))
      (node (ref "U1") (pin "8") (pinfunction "PB7(XTAL2/TOSC2)_8") (pintype "bidirectional"))
    )
    (net (code "31") (name "Net-(U3-DO)") (class "Default")
      (node (ref "U3") (pin "1") (pinfunction "DO_1") (pintype "output"))
      (node (ref "U4") (pin "3") (pinfunction "DI_3") (pintype "input"))
    )
    (net (code "32") (name "Net-(U4-DO)") (class "Default")
      (node (ref "U4") (pin "1") (pinfunction "DO_1") (pintype "output"))
      (node (ref "U9") (pin "3") (pinfunction "DI_3") (pintype "input"))
    )
    (net (code "33") (name "Net-(U10-DI)") (class "Default")
      (node (ref "U10") (pin "3") (pinfunction "DI_3") (pintype "input"))
      (node (ref "U9") (pin "1") (pinfunction "DO_1") (pintype "output"))
    )
    (net (code "34") (name "Net-(U10-DO)") (class "Default")
      (node (ref "U10") (pin "1") (pinfunction "DO_1") (pintype "output"))
      (node (ref "U11") (pin "3") (pinfunction "DI_3") (pintype "input"))
    )
    (net (code "35") (name "Net-(U11-DO)") (class "Default")
      (node (ref "U11") (pin "1") (pinfunction "DO_1") (pintype "output"))
      (node (ref "U12") (pin "3") (pinfunction "DI_3") (pintype "input"))
    )
    (net (code "36") (name "Net-(U12-DO)") (class "Default")
      (node (ref "U12") (pin "1") (pinfunction "DO_1") (pintype "output"))
      (node (ref "U13") (pin "3") (pinfunction "DI_3") (pintype "input"))
    )
    (net (code "37") (name "Net-(U13-DO)") (class "Default")
      (node (ref "U13") (pin "1") (pinfunction "DO_1") (pintype "output"))
      (node (ref "U14") (pin "3") (pinfunction "DI_3") (pintype "input"))
    )
    (net (code "38") (name "Net-(U14-DO)") (class "Default")
      (node (ref "U14") (pin "1") (pinfunction "DO_1") (pintype "output"))
      (node (ref "U15") (pin "3") (pinfunction "DI_3") (pintype "input"))
    )
    (net (code "39") (name "Net-(U15-DO)") (class "Default")
      (node (ref "U15") (pin "1") (pinfunction "DO_1") (pintype "output"))
      (node (ref "U16") (pin "3") (pinfunction "DI_3") (pintype "input"))
    )
    (net (code "40") (name "Net-(U16-DO)") (class "Default")
      (node (ref "U16") (pin "1") (pinfunction "DO_1") (pintype "output"))
      (node (ref "U17") (pin "3") (pinfunction "DI_3") (pintype "input"))
    )
    (net (code "41") (name "Net-(U17-DO)") (class "Default")
      (node (ref "U17") (pin "1") (pinfunction "DO_1") (pintype "output"))
      (node (ref "U18") (pin "3") (pinfunction "DI_3") (pintype "input"))
    )
    (net (code "42") (name "Net-(U18-DO)") (class "Default")
      (node (ref "U18") (pin "1") (pinfunction "DO_1") (pintype "output"))
      (node (ref "U19") (pin "3") (pinfunction "DI_3") (pintype "input"))
    )
    (net (code "43") (name "Net-(U19-DO)") (class "Default")
      (node (ref "U19") (pin "1") (pinfunction "DO_1") (pintype "output"))
      (node (ref "U20") (pin "3") (pinfunction "DI_3") (pintype "input"))
    )
    (net (code "44") (name "Net-(U20-DO)") (class "Default")
      (node (ref "U20") (pin "1") (pinfunction "DO_1") (pintype "output"))
      (node (ref "U21") (pin "3") (pinfunction "DI_3") (pintype "input"))
    )
    (net (code "45") (name "Net-(U21-DO)") (class "Default")
      (node (ref "U21") (pin "1") (pinfunction "DO_1") (pintype "output"))
      (node (ref "U22") (pin "3") (pinfunction "DI_3") (pintype "input"))
    )
    (net (code "46") (name "PE0") (class "Default")
      (node (ref "TP2") (pin "TP") (pinfunction "TP_TP") (pintype "input"))
      (node (ref "U1") (pin "3") (pinfunction "GND_3") (pintype "bidirectional"))
    )
    (net (code "47") (name "PE1") (class "Default")
      (node (ref "TP1") (pin "TP") (pinfunction "TP_TP") (pintype "input"))
      (node (ref "U1") (pin "6") (pinfunction "VCC_6") (pintype "bidirectional"))
    )
    (net (code "48") (name "RESET") (class "Default")
      (node (ref "C2") (pin "1") (pinfunction "1_1") (pintype "passive"))
      (node (ref "J1") (pin "1") (pinfunction "1_1") (pintype "passive"))
      (node (ref "R2") (pin "1") (pinfunction "1_1") (pintype "passive"))
      (node (ref "S1") (pin "4") (pinfunction "4_4") (pintype "passive"))
      (node (ref "U1") (pin "29") (pinfunction "PC6(/RESET)_29") (pintype "bidirectional"))
    )
    (net (code "49") (name "RXI") (class "Default")
      (node (ref "JP3") (pin "1") (pinfunction "1_1") (pintype "passive"))
      (node (ref "U1") (pin "30") (pinfunction "PD0(RXD)_30") (pintype "bidirectional"))
    )
    (net (code "50") (name "SAO_IO1") (class "Default")
      (node (ref "J1") (pin "4") (pinfunction "4_4") (pintype "passive"))
      (node (ref "J2") (pin "5") (pinfunction "5_5") (pintype "passive"))
      (node (ref "U1") (pin "15") (pinfunction "PB3(MOSI/OC2)_15") (pintype "bidirectional"))
    )
    (net (code "51") (name "SAO_IO2") (class "Default")
      (node (ref "J1") (pin "5") (pinfunction "5_5") (pintype "passive"))
      (node (ref "J2") (pin "6") (pinfunction "6_6") (pintype "passive"))
      (node (ref "U1") (pin "16") (pinfunction "PB4(MISO)_16") (pintype "bidirectional"))
    )
    (net (code "52") (name "SCL") (class "Default")
      (node (ref "J2") (pin "4") (pinfunction "4_4") (pintype "passive"))
      (node (ref "SV3") (pin "2") (pinfunction "2_2") (pintype "passive"))
      (node (ref "U1") (pin "28") (pinfunction "PC5(ADC5/SCL)_28") (pintype "bidirectional"))
    )
    (net (code "53") (name "SDA") (class "Default")
      (node (ref "J2") (pin "3") (pinfunction "3_3") (pintype "passive"))
      (node (ref "SV3") (pin "1") (pinfunction "1_1") (pintype "passive"))
      (node (ref "U1") (pin "27") (pinfunction "PC4(ADC4/SDA)_27") (pintype "bidirectional"))
    )
    (net (code "54") (name "SIG_IN1") (class "Default")
      (node (ref "SV2") (pin "5") (pinfunction "5_5") (pintype "passive"))
      (node (ref "U1") (pin "32") (pinfunction "PD2(INT0)_32") (pintype "bidirectional"))
    )
    (net (code "55") (name "SIG_IN2") (class "Default")
      (node (ref "SV2") (pin "4") (pinfunction "4_4") (pintype "passive"))
      (node (ref "U1") (pin "1") (pinfunction "PD3(INT1)_1") (pintype "bidirectional"))
    )
    (net (code "56") (name "SIG_IN3") (class "Default")
      (node (ref "SV2") (pin "3") (pinfunction "3_3") (pintype "passive"))
      (node (ref "U1") (pin "2") (pinfunction "PD4(XCK/T0)_2") (pintype "bidirectional"))
    )
    (net (code "57") (name "SIG_OUT1") (class "Default")
      (node (ref "SV1") (pin "1") (pinfunction "1_1") (pintype "passive"))
      (node (ref "U1") (pin "9") (pinfunction "PD5(T1)_9") (pintype "bidirectional"))
    )
    (net (code "58") (name "SIG_OUT2") (class "Default")
      (node (ref "SV1") (pin "2") (pinfunction "2_2") (pintype "passive"))
      (node (ref "U1") (pin "10") (pinfunction "PD6(AIN0)_10") (pintype "bidirectional"))
    )
    (net (code "59") (name "SIG_OUT3") (class "Default")
      (node (ref "SV1") (pin "3") (pinfunction "3_3") (pintype "passive"))
      (node (ref "U1") (pin "11") (pinfunction "PD7(AIN1)_11") (pintype "bidirectional"))
    )
    (net (code "60") (name "TXO") (class "Default")
      (node (ref "JP2") (pin "1") (pinfunction "1_1") (pintype "passive"))
      (node (ref "U1") (pin "31") (pinfunction "PD1(TXD)_31") (pintype "bidirectional"))
    )
    (net (code "61") (name "USB_DN") (class "Default")
      (node (ref "J3") (pin "A7") (pinfunction "DN1_A7") (pintype "bidirectional"))
      (node (ref "J3") (pin "B7") (pinfunction "DN2_B7") (pintype "bidirectional"))
      (node (ref "U7") (pin "6") (pinfunction "UD-_6") (pintype "bidirectional"))
      (node (ref "U8") (pin "6") (pinfunction "C5_6") (pintype "passive"))
    )
    (net (code "62") (name "USB_DP") (class "Default")
      (node (ref "J3") (pin "A6") (pinfunction "DP1_A6") (pintype "bidirectional"))
      (node (ref "J3") (pin "B6") (pinfunction "DP2_B6") (pintype "bidirectional"))
      (node (ref "U7") (pin "5") (pinfunction "UD+_5") (pintype "bidirectional"))
      (node (ref "U8") (pin "5") (pinfunction "C4_5") (pintype "passive"))
    )
    (net (code "63") (name "VBAT") (class "Default")
      (node (ref "D4") (pin "A") (pinfunction "A_A") (pintype "passive"))
      (node (ref "U6") (pin "1") (pinfunction "1_1") (pintype "passive"))
    )
    (net (code "64") (name "VBUS") (class "Default")
      (node (ref "D3") (pin "A") (pinfunction "A_A") (pintype "passive"))
      (node (ref "J3") (pin "A4/B9") (pinfunction "VBUS_A4/B9") (pintype "power_in"))
      (node (ref "J3") (pin "B4/A9") (pinfunction "VBUS_B4/A9") (pintype "power_in"))
      (node (ref "U8") (pin "4") (pinfunction "C3_4") (pintype "passive"))
    )
    (net (code "65") (name "VDD") (class "Default")
      (node (ref "C10") (pin "2") (pinfunction "2_2") (pintype "passive"))
      (node (ref "C11") (pin "2") (pinfunction "2_2") (pintype "passive"))
      (node (ref "C12") (pin "2") (pinfunction "2_2") (pintype "passive"))
      (node (ref "C13") (pin "2") (pinfunction "2_2") (pintype "passive"))
      (node (ref "C14") (pin "2") (pinfunction "2_2") (pintype "passive"))
      (node (ref "C15") (pin "2") (pinfunction "2_2") (pintype "passive"))
      (node (ref "C16") (pin "2") (pinfunction "2_2") (pintype "passive"))
      (node (ref "C17") (pin "2") (pinfunction "2_2") (pintype "passive"))
      (node (ref "C18") (pin "2") (pinfunction "2_2") (pintype "passive"))
      (node (ref "C19") (pin "2") (pinfunction "2_2") (pintype "passive"))
      (node (ref "C21") (pin "1") (pinfunction "1_1") (pintype "passive"))
      (node (ref "C4") (pin "2") (pinfunction "2_2") (pintype "passive"))
      (node (ref "C5") (pin "2") (pinfunction "2_2") (pintype "passive"))
      (node (ref "C6") (pin "2") (pinfunction "2_2") (pintype "passive"))
      (node (ref "C7") (pin "2") (pinfunction "2_2") (pintype "passive"))
      (node (ref "C8") (pin "2") (pinfunction "2_2") (pintype "passive"))
      (node (ref "C9") (pin "2") (pinfunction "2_2") (pintype "passive"))
      (node (ref "D5") (pin "A") (pinfunction "A_A") (pintype "passive"))
      (node (ref "R7") (pin "2") (pinfunction "2_2") (pintype "passive"))
      (node (ref "U10") (pin "4") (pinfunction "VDD_4") (pintype "power_in"))
      (node (ref "U11") (pin "4") (pinfunction "VDD_4") (pintype "power_in"))
      (node (ref "U12") (pin "4") (pinfunction "VDD_4") (pintype "power_in"))
      (node (ref "U13") (pin "4") (pinfunction "VDD_4") (pintype "power_in"))
      (node (ref "U14") (pin "4") (pinfunction "VDD_4") (pintype "power_in"))
      (node (ref "U15") (pin "4") (pinfunction "VDD_4") (pintype "power_in"))
      (node (ref "U16") (pin "4") (pinfunction "VDD_4") (pintype "power_in"))
      (node (ref "U17") (pin "4") (pinfunction "VDD_4") (pintype "power_in"))
      (node (ref "U18") (pin "4") (pinfunction "VDD_4") (pintype "power_in"))
      (node (ref "U19") (pin "4") (pinfunction "VDD_4") (pintype "power_in"))
      (node (ref "U2") (pin "1") (pinfunction "IN_1") (pintype "power_in"))
      (node (ref "U20") (pin "4") (pinfunction "VDD_4") (pintype "power_in"))
      (node (ref "U21") (pin "4") (pinfunction "VDD_4") (pintype "power_in"))
      (node (ref "U22") (pin "4") (pinfunction "VDD_4") (pintype "power_in"))
      (node (ref "U3") (pin "4") (pinfunction "VDD_4") (pintype "power_in"))
      (node (ref "U4") (pin "4") (pinfunction "VDD_4") (pintype "power_in"))
      (node (ref "U5") (pin "1") (pinfunction "1_1") (pintype "passive"))
      (node (ref "U9") (pin "4") (pinfunction "VDD_4") (pintype "power_in"))
    )
    (net (code "66") (name "unconnected-(J3-SBU1-PadA8)") (class "Default")
      (node (ref "J3") (pin "A8") (pinfunction "SBU1_A8") (pintype "bidirectional"))
    )
    (net (code "67") (name "unconnected-(J3-SBU2-PadB8)") (class "Default")
      (node (ref "J3") (pin "B8") (pinfunction "SBU2_B8") (pintype "bidirectional"))
    )
    (net (code "68") (name "unconnected-(S1-Pad1)") (class "Default")
      (node (ref "S1") (pin "1") (pinfunction "1_1") (pintype "passive"))
    )
    (net (code "69") (name "unconnected-(S1-Pad3)") (class "Default")
      (node (ref "S1") (pin "3") (pinfunction "3_3") (pintype "passive"))
    )
    (net (code "70") (name "unconnected-(S2-Pad1)") (class "Default")
      (node (ref "S2") (pin "1") (pinfunction "1_1") (pintype "passive"))
    )
    (net (code "71") (name "unconnected-(S2-Pad3)") (class "Default")
      (node (ref "S2") (pin "3") (pinfunction "3_3") (pintype "passive"))
    )
    (net (code "72") (name "unconnected-(S3-Pad1)") (class "Default")
      (node (ref "S3") (pin "1") (pinfunction "1_1") (pintype "passive"))
    )
    (net (code "73") (name "unconnected-(S3-Pad3)") (class "Default")
      (node (ref "S3") (pin "3") (pinfunction "3_3") (pintype "passive"))
    )
    (net (code "74") (name "unconnected-(S4-Pad1)") (class "Default")
      (node (ref "S4") (pin "1") (pinfunction "1_1") (pintype "passive"))
    )
    (net (code "75") (name "unconnected-(S4-Pad3)") (class "Default")
      (node (ref "S4") (pin "3") (pinfunction "3_3") (pintype "passive"))
    )
    (net (code "76") (name "unconnected-(S5-Pad1)") (class "Default")
      (node (ref "S5") (pin "1") (pinfunction "1_1") (pintype "passive"))
    )
    (net (code "77") (name "unconnected-(S5-Pad3)") (class "Default")
      (node (ref "S5") (pin "3") (pinfunction "3_3") (pintype "passive"))
    )
    (net (code "78") (name "unconnected-(S6-Pad1)") (class "Default")
      (node (ref "S6") (pin "1") (pinfunction "1_1") (pintype "passive"))
    )
    (net (code "79") (name "unconnected-(S6-Pad3)") (class "Default")
      (node (ref "S6") (pin "3") (pinfunction "3_3") (pintype "passive"))
    )
    (net (code "80") (name "unconnected-(S7-Pad1)") (class "Default")
      (node (ref "S7") (pin "1") (pinfunction "1_1") (pintype "passive"))
    )
    (net (code "81") (name "unconnected-(S7-Pad3)") (class "Default")
      (node (ref "S7") (pin "3") (pinfunction "3_3") (pintype "passive"))
    )
    (net (code "82") (name "unconnected-(SV1-Pad5)") (class "Default")
      (node (ref "SV1") (pin "5") (pinfunction "5_5") (pintype "passive"))
    )
    (net (code "83") (name "unconnected-(SV2-Pad1)") (class "Default")
      (node (ref "SV2") (pin "1") (pinfunction "1_1") (pintype "passive"))
    )
    (net (code "84") (name "unconnected-(U1-PB0(ICP)-Pad12)") (class "Default")
      (node (ref "U1") (pin "12") (pinfunction "PB0(ICP)_12") (pintype "bidirectional"))
    )
    (net (code "85") (name "unconnected-(U1-PB2(SS{slash}OC1B)-Pad14)") (class "Default")
      (node (ref "U1") (pin "14") (pinfunction "PB2(SS/OC1B)_14") (pintype "bidirectional"))
    )
    (net (code "86") (name "unconnected-(U2-P4-Pad4)") (class "Default")
      (node (ref "U2") (pin "4") (pinfunction "P4_4") (pintype "bidirectional"))
    )
    (net (code "87") (name "unconnected-(U5-Pad3)") (class "Default")
      (node (ref "U5") (pin "3") (pinfunction "3_3") (pintype "passive"))
    )
    (net (code "88") (name "unconnected-(U7-NC.-Pad7)") (class "Default")
      (node (ref "U7") (pin "7") (pinfunction "NC._7") (pintype "no_connect"))
    )
    (net (code "89") (name "unconnected-(U7-R232-Pad15)") (class "Default")
      (node (ref "U7") (pin "15") (pinfunction "R232_15") (pintype "input"))
    )
    (net (code "90") (name "unconnected-(U7-~{CTS}-Pad9)") (class "Default")
      (node (ref "U7") (pin "9") (pinfunction "~{CTS}_9") (pintype "input"))
    )
    (net (code "91") (name "unconnected-(U7-~{DCD}-Pad12)") (class "Default")
      (node (ref "U7") (pin "12") (pinfunction "~{DCD}_12") (pintype "input"))
    )
    (net (code "92") (name "unconnected-(U7-~{DSR}-Pad10)") (class "Default")
      (node (ref "U7") (pin "10") (pinfunction "~{DSR}_10") (pintype "input"))
    )
    (net (code "93") (name "unconnected-(U7-~{OUT}-Pad8)") (class "Default")
      (node (ref "U7") (pin "8") (pinfunction "~{OUT}_8") (pintype "output"))
    )
    (net (code "94") (name "unconnected-(U7-~{RI}-Pad11)") (class "Default")
      (node (ref "U7") (pin "11") (pinfunction "~{RI}_11") (pintype "input"))
    )
    (net (code "95") (name "unconnected-(U7-~{RTS}-Pad14)") (class "Default")
      (node (ref "U7") (pin "14") (pinfunction "~{RTS}_14") (pintype "output"))
    )
    (net (code "96") (name "unconnected-(U8-C1-Pad1)") (class "Default")
      (node (ref "U8") (pin "1") (pinfunction "C1_1") (pintype "passive"))
    )
    (net (code "97") (name "unconnected-(U8-C2-Pad3)") (class "Default")
      (node (ref "U8") (pin "3") (pinfunction "C2_3") (pintype "passive"))
    )
    (net (code "98") (name "unconnected-(U22-DO-Pad1)") (class "Default")
      (node (ref "U22") (pin "1") (pinfunction "DO_1") (pintype "output"))
    )
  )
)
